# SCH_ESP-RotaryCell-Main-Carrier-Rev-A1_2.net
KiCad netlist of a schematic drawn in EasyEDA
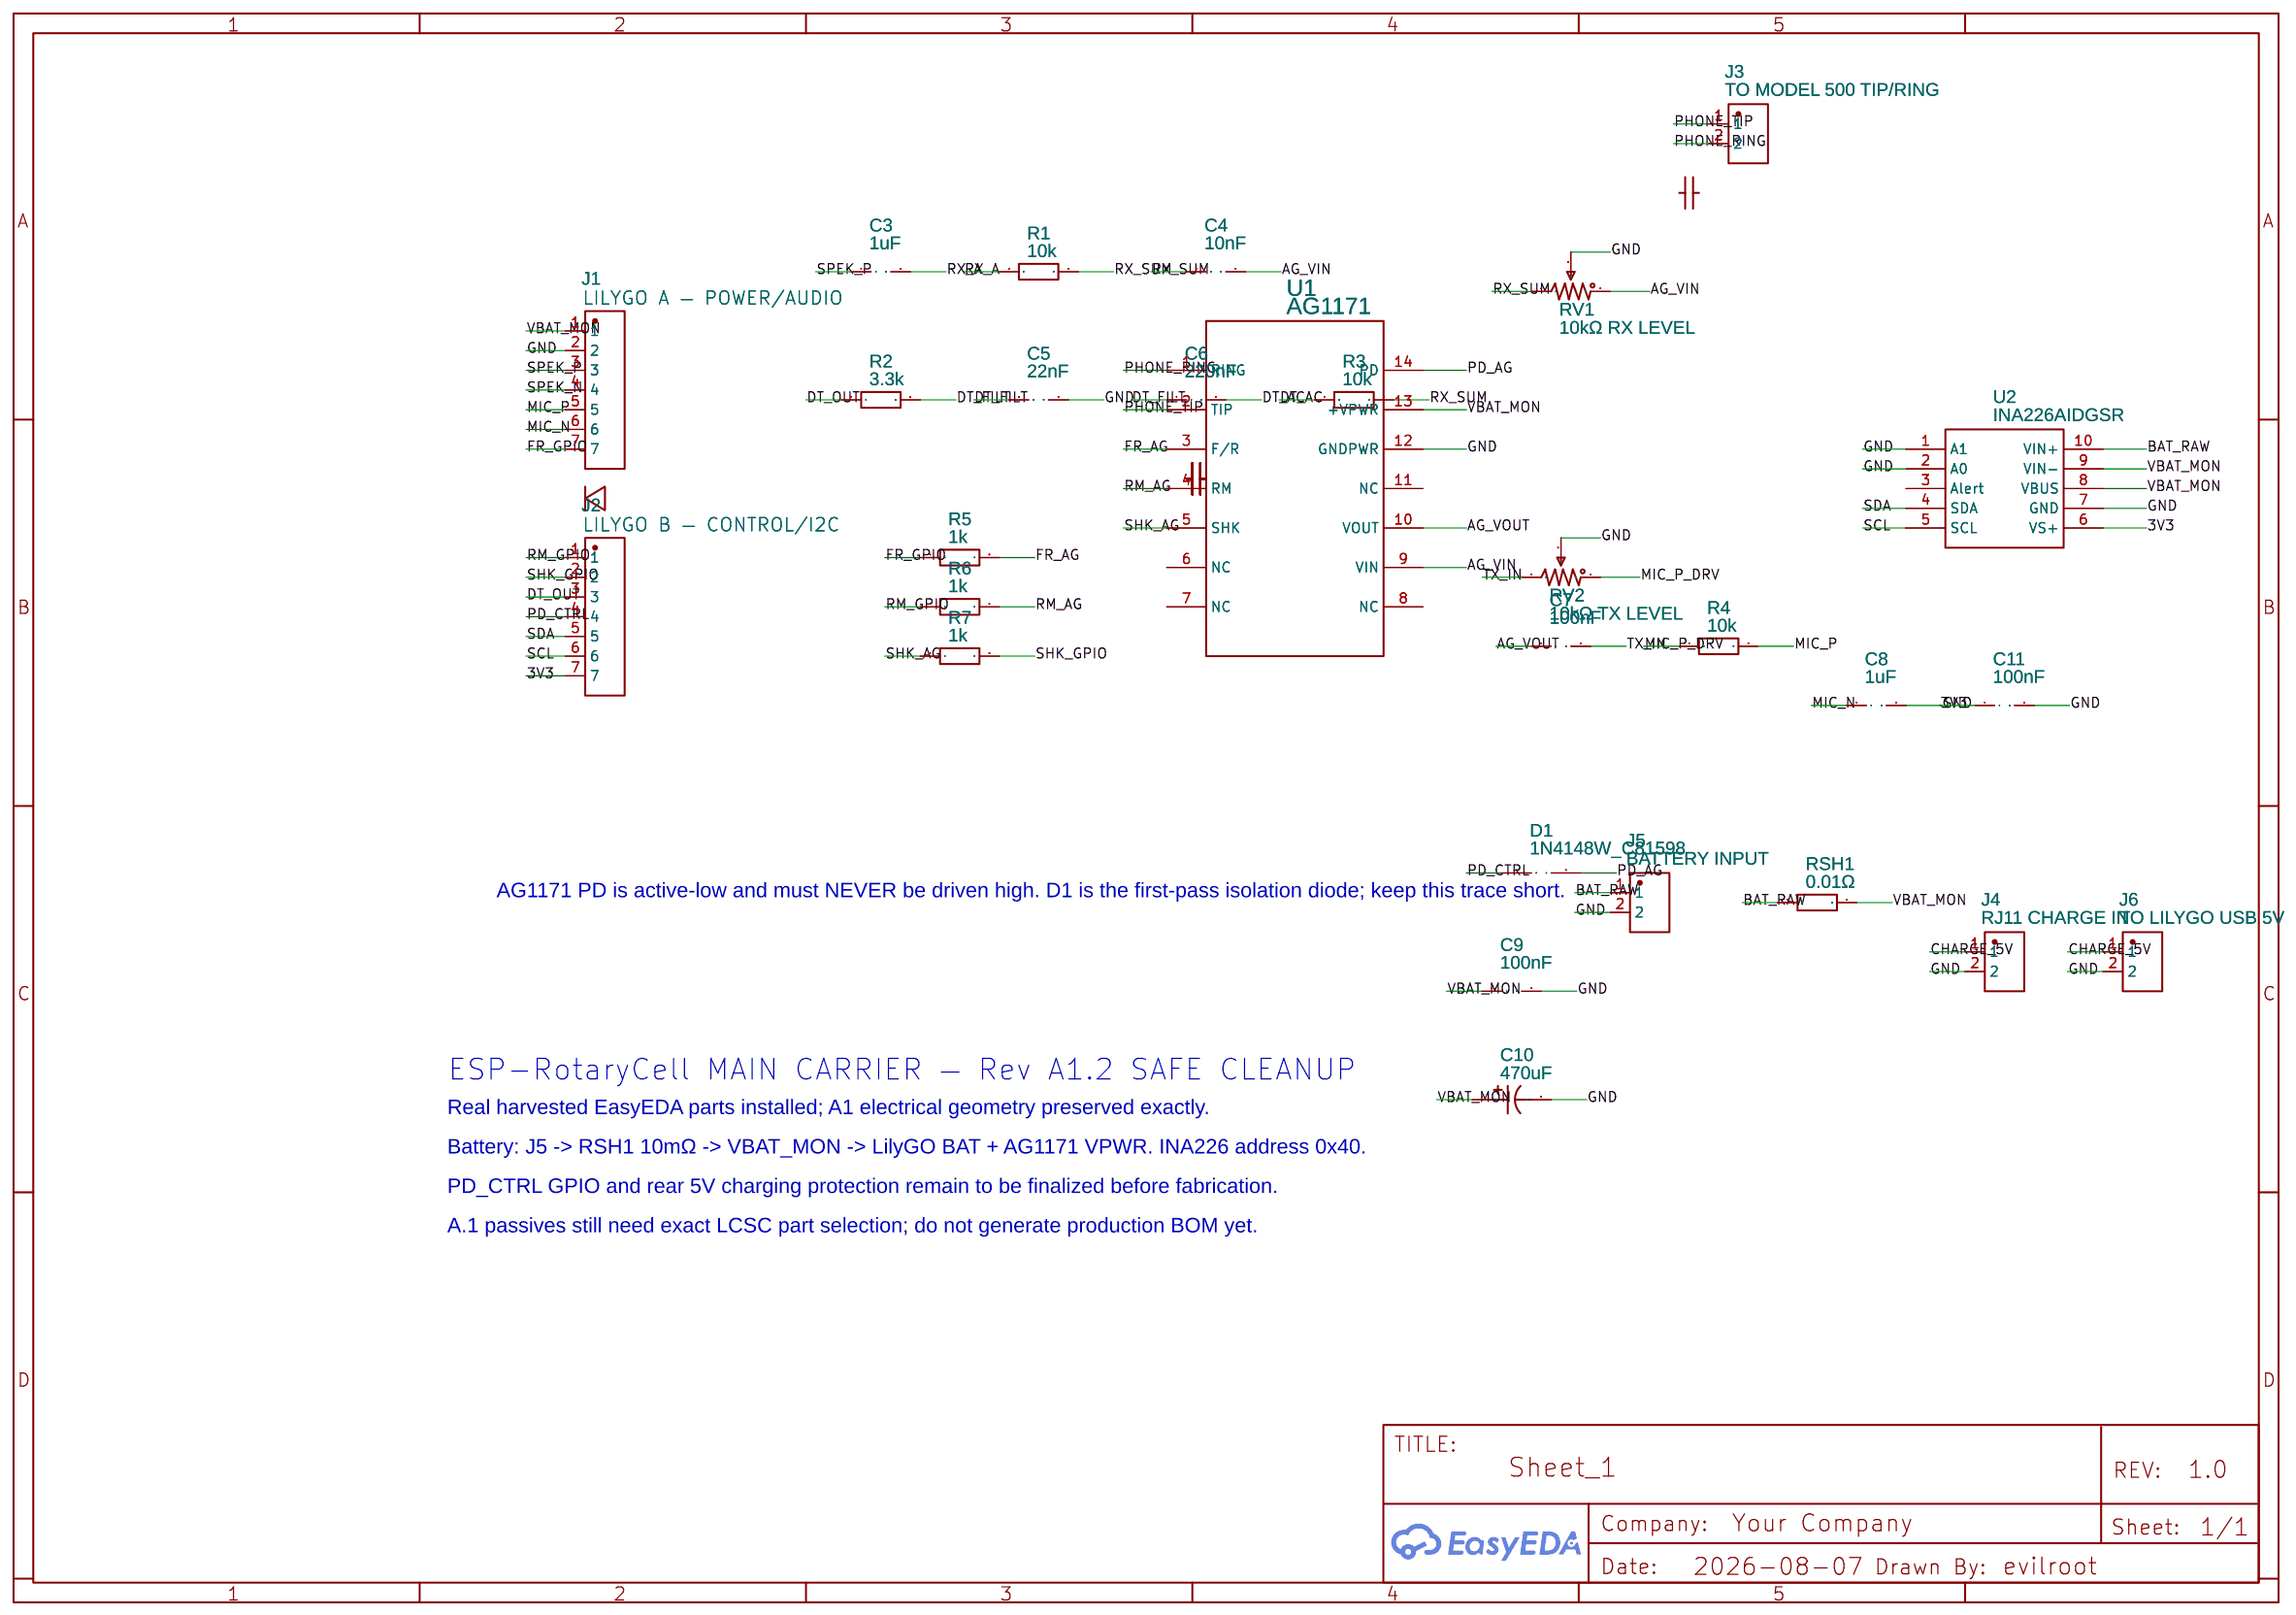
[diagram p0: schematic sheet]

(export (version "E")
  (design (tool "Eeschema 10.0.6"))
  (components
    (comp (ref "C3") (value "1uF") (libsource (lib "") (part "Unknown_440_-675")))
    (comp (ref "C4") (value "10nF") (libsource (lib "") (part "Unknown_610_-675")))
    (comp (ref "C5") (value "22nF") (libsource (lib "") (part "Unknown_520_-610")))
    (comp (ref "C6") (value "220nF") (libsource (lib "") (part "Unknown_600_-610")))
    (comp (ref "C7") (value "100nF") (libsource (lib "") (part "Unknown_785_-485")))
    (comp (ref "C8") (value "1uF") (libsource (lib "") (part "Unknown_945_-455")))
    (comp (ref "C9") (value "100nF") (libsource (lib "") (part "Unknown_760_-310")))
    (comp (ref "C10")
      (value "470uF")
      (fields
        (field (name "Manufacturer Part") "RYHT16V470UF5.5*11")
        (field (name "Manufacturer") "HONOR(荣誉)")
      )
      (libsource (lib "") (part "RYHT16V470UF5.5*11"))
    )
    (comp (ref "C11") (value "100nF") (libsource (lib "") (part "Unknown_1010_-455")))
    (comp (ref "D1")
      (value "1N4148W_C81598")
      (fields (field (name "Manufacturer Part") "1N4148W") (field (name "Manufacturer") "ST(先科)"))
      (libsource (lib "") (part "1N4148W_C81598"))
    )
    (comp (ref "J1")
      (value "LILYGO A — POWER/AUDIO")
      (fields
        (field (name "Manufacturer Part") "PM2.54-1x7PZZ-H8.5")
        (field (name "Manufacturer") "SHOU HAN(首韩)")
      )
      (libsource (lib "") (part "PM2.54-1X7PZZ-H8.5"))
    )
    (comp (ref "J2")
      (value "LILYGO B — CONTROL/I2C")
      (fields
        (field (name "Manufacturer Part") "PM2.54-1x7PZZ-H8.5")
        (field (name "Manufacturer") "SHOU HAN(首韩)")
      )
      (libsource (lib "") (part "PM2.54-1X7PZZ-H8.5"))
    )
    (comp (ref "J3")
      (value "TO MODEL 500 TIP/RING")
      (fields
        (field (name "Manufacturer Part") "HMT-2.54-1*2PM")
        (field (name "Manufacturer") "HMTCONN(华明通)")
      )
      (libsource (lib "") (part "HMT-2.54-1*2PM"))
    )
    (comp (ref "J4")
      (value "RJ11 CHARGE IN")
      (fields
        (field (name "Manufacturer Part") "HMT-2.54-1*2PM")
        (field (name "Manufacturer") "HMTCONN(华明通)")
      )
      (libsource (lib "") (part "HMT-2.54-1*2PM"))
    )
    (comp (ref "J5")
      (value "BATTERY INPUT")
      (fields
        (field (name "Manufacturer Part") "HMT-2.54-1*2PM")
        (field (name "Manufacturer") "HMTCONN(华明通)")
      )
      (libsource (lib "") (part "HMT-2.54-1*2PM"))
    )
    (comp (ref "J6")
      (value "TO LILYGO USB 5V")
      (fields
        (field (name "Manufacturer Part") "HMT-2.54-1*2PM")
        (field (name "Manufacturer") "HMTCONN(华明通)")
      )
      (libsource (lib "") (part "HMT-2.54-1*2PM"))
    )
    (comp (ref "R1") (value "10k") (libsource (lib "") (part "Unknown_520_-675")))
    (comp (ref "R2") (value "3.3k") (libsource (lib "") (part "Unknown_440_-610")))
    (comp (ref "R3") (value "10k") (libsource (lib "") (part "Unknown_680_-610")))
    (comp (ref "R4") (value "10k") (libsource (lib "") (part "Unknown_865_-485")))
    (comp (ref "R5") (value "1k") (libsource (lib "") (part "Unknown_480_-530")))
    (comp (ref "R6") (value "1k") (libsource (lib "") (part "Unknown_480_-505")))
    (comp (ref "R7") (value "1k") (libsource (lib "") (part "Unknown_480_-480")))
    (comp (ref "RSH1")
      (value "0.01Ω")
      (fields (field (name "Manufacturer Part") "MRF6432(2512)LR010JTS") (field (name "Manufacturer") "SUP"))
      (libsource (lib "") (part "MRF6432(2512)LR010JTS"))
    )
    (comp (ref "RV1")
      (value "10kΩ RX LEVEL")
      (fields (field (name "Manufacturer Part") "PS10KV50-103A3030") (field (name "Manufacturer") "Amphenol"))
      (libsource (lib "") (part "PS10KV50-103A3030"))
    )
    (comp (ref "RV2")
      (value "10kΩ TX LEVEL")
      (fields (field (name "Manufacturer Part") "PS10KV50-103A3030") (field (name "Manufacturer") "Amphenol"))
      (libsource (lib "") (part "PS10KV50-103A3030"))
    )
    (comp (ref "U1")
      (value "AG1171")
      (fields (field (name "Manufacturer Part") "Ag1171") (field (name "Manufacturer") "Silver Telecom"))
      (libsource (lib "") (part "AG1171"))
    )
    (comp (ref "U2")
      (value "INA226AIDGSR")
      (fields (field (name "Manufacturer") "TI(德州仪器)"))
      (libsource (lib "") (part "INA226AIDGSR"))
    )
  )
  (nets
    (net (code "1") (name "/3V3") (class "Default")
      (node (ref "C10") (pin "2") (pinfunction "2_2") (pintype "input"))
      (node (ref "C11") (pin "1") (pinfunction "1_1") (pintype "input"))
      (node (ref "C11") (pin "2") (pinfunction "2_2") (pintype "input"))
      (node (ref "C5") (pin "2") (pinfunction "2_2") (pintype "input"))
      (node (ref "C8") (pin "2") (pinfunction "2_2") (pintype "input"))
      (node (ref "C9") (pin "2") (pinfunction "2_2") (pintype "input"))
      (node (ref "J1") (pin "2") (pinfunction "2_2") (pintype "unspecified"))
      (node (ref "J2") (pin "7") (pinfunction "7_7") (pintype "unspecified"))
      (node (ref "J4") (pin "2") (pinfunction "2_2") (pintype "unspecified"))
      (node (ref "J5") (pin "2") (pinfunction "2_2") (pintype "unspecified"))
      (node (ref "J6") (pin "2") (pinfunction "2_2") (pintype "unspecified"))
      (node (ref "RV1") (pin "3") (pinfunction "3_3") (pintype "unspecified"))
      (node (ref "RV2") (pin "3") (pinfunction "3_3") (pintype "unspecified"))
      (node (ref "U1") (pin "12") (pinfunction "GNDPWR_12") (pintype "unspecified"))
      (node (ref "U2") (pin "1") (pinfunction "A1_1") (pintype "unspecified"))
      (node (ref "U2") (pin "2") (pinfunction "A0_2") (pintype "unspecified"))
      (node (ref "U2") (pin "6") (pinfunction "VS+_6") (pintype "unspecified"))
      (node (ref "U2") (pin "7") (pinfunction "GND_7") (pintype "unspecified"))
    )
    (net (code "2") (name "/AG_VIN") (class "Default")
      (node (ref "C4") (pin "2") (pinfunction "2_2") (pintype "input"))
      (node (ref "RV1") (pin "2") (pinfunction "2_2") (pintype "unspecified"))
      (node (ref "U1") (pin "9") (pinfunction "VIN_9") (pintype "unspecified"))
    )
    (net (code "3") (name "/AG_VOUT") (class "Default")
      (node (ref "C7") (pin "1") (pinfunction "1_1") (pintype "input"))
      (node (ref "U1") (pin "10") (pinfunction "VOUT_10") (pintype "unspecified"))
    )
    (net (code "4") (name "/BAT_RAW") (class "Default")
      (node (ref "J5") (pin "1") (pinfunction "1_1") (pintype "unspecified"))
      (node (ref "RSH1") (pin "1") (pinfunction "1_1") (pintype "input"))
      (node (ref "U2") (pin "10") (pinfunction "VIN+_10") (pintype "unspecified"))
    )
    (net (code "5") (name "/CHARGE_5V") (class "Default")
      (node (ref "J4") (pin "1") (pinfunction "1_1") (pintype "unspecified"))
      (node (ref "J6") (pin "1") (pinfunction "1_1") (pintype "unspecified"))
    )
    (net (code "6") (name "/DT_AC") (class "Default")
      (node (ref "C6") (pin "2") (pinfunction "2_2") (pintype "input"))
      (node (ref "R3") (pin "1") (pinfunction "1_1") (pintype "input"))
    )
    (net (code "7") (name "/DT_FILT") (class "Default")
      (node (ref "C5") (pin "1") (pinfunction "1_1") (pintype "input"))
      (node (ref "C6") (pin "1") (pinfunction "1_1") (pintype "input"))
      (node (ref "R2") (pin "2") (pinfunction "2_2") (pintype "input"))
    )
    (net (code "8") (name "/DT_OUT") (class "Default")
      (node (ref "J2") (pin "3") (pinfunction "3_3") (pintype "unspecified"))
      (node (ref "R2") (pin "1") (pinfunction "1_1") (pintype "input"))
    )
    (net (code "9") (name "/FR_AG") (class "Default")
      (node (ref "R5") (pin "2") (pinfunction "2_2") (pintype "input"))
      (node (ref "U1") (pin "3") (pinfunction "F/R_3") (pintype "unspecified"))
    )
    (net (code "10") (name "/FR_GPIO") (class "Default")
      (node (ref "J1") (pin "7") (pinfunction "7_7") (pintype "unspecified"))
      (node (ref "R5") (pin "1") (pinfunction "1_1") (pintype "input"))
    )
    (net (code "11") (name "/MIC_N") (class "Default")
      (node (ref "C8") (pin "1") (pinfunction "1_1") (pintype "input"))
      (node (ref "J1") (pin "6") (pinfunction "6_6") (pintype "unspecified"))
    )
    (net (code "12") (name "/MIC_P") (class "Default")
      (node (ref "J1") (pin "5") (pinfunction "5_5") (pintype "unspecified"))
      (node (ref "R4") (pin "2") (pinfunction "2_2") (pintype "input"))
    )
    (net (code "13") (name "/MIC_P_DRV") (class "Default")
      (node (ref "R4") (pin "1") (pinfunction "1_1") (pintype "input"))
      (node (ref "RV2") (pin "2") (pinfunction "2_2") (pintype "unspecified"))
    )
    (net (code "14") (name "/PD_AG") (class "Default")
      (node (ref "D1") (pin "2") (pinfunction "A_2") (pintype "unspecified"))
      (node (ref "U1") (pin "14") (pinfunction "PD_14") (pintype "unspecified"))
    )
    (net (code "15") (name "/PD_CTRL") (class "Default")
      (node (ref "D1") (pin "1") (pinfunction "K_1") (pintype "unspecified"))
      (node (ref "J2") (pin "4") (pinfunction "4_4") (pintype "unspecified"))
    )
    (net (code "16") (name "/PHONE_RING") (class "Default")
      (node (ref "J3") (pin "2") (pinfunction "2_2") (pintype "unspecified"))
      (node (ref "U1") (pin "1") (pinfunction "RING_1") (pintype "unspecified"))
    )
    (net (code "17") (name "/PHONE_TIP") (class "Default")
      (node (ref "J3") (pin "1") (pinfunction "1_1") (pintype "unspecified"))
      (node (ref "U1") (pin "2") (pinfunction "TIP_2") (pintype "unspecified"))
    )
    (net (code "18") (name "/RM_AG") (class "Default")
      (node (ref "R6") (pin "2") (pinfunction "2_2") (pintype "input"))
      (node (ref "U1") (pin "4") (pinfunction "RM_4") (pintype "unspecified"))
    )
    (net (code "19") (name "/RM_GPIO") (class "Default")
      (node (ref "J2") (pin "1") (pinfunction "1_1") (pintype "unspecified"))
      (node (ref "R6") (pin "1") (pinfunction "1_1") (pintype "input"))
    )
    (net (code "20") (name "/RX_A") (class "Default")
      (node (ref "C3") (pin "2") (pinfunction "2_2") (pintype "input"))
      (node (ref "R1") (pin "1") (pinfunction "1_1") (pintype "input"))
    )
    (net (code "21") (name "/RX_SUM") (class "Default")
      (node (ref "C4") (pin "1") (pinfunction "1_1") (pintype "input"))
      (node (ref "R1") (pin "2") (pinfunction "2_2") (pintype "input"))
      (node (ref "R3") (pin "2") (pinfunction "2_2") (pintype "input"))
      (node (ref "RV1") (pin "1") (pinfunction "1_1") (pintype "unspecified"))
    )
    (net (code "22") (name "/SCL") (class "Default")
      (node (ref "J2") (pin "6") (pinfunction "6_6") (pintype "unspecified"))
      (node (ref "U2") (pin "5") (pinfunction "SCL_5") (pintype "unspecified"))
    )
    (net (code "23") (name "/SDA") (class "Default")
      (node (ref "J2") (pin "5") (pinfunction "5_5") (pintype "unspecified"))
      (node (ref "U2") (pin "4") (pinfunction "SDA_4") (pintype "unspecified"))
    )
    (net (code "24") (name "/SHK_AG") (class "Default")
      (node (ref "R7") (pin "1") (pinfunction "1_1") (pintype "input"))
      (node (ref "U1") (pin "5") (pinfunction "SHK_5") (pintype "unspecified"))
    )
    (net (code "25") (name "/SHK_GPIO") (class "Default")
      (node (ref "J2") (pin "2") (pinfunction "2_2") (pintype "unspecified"))
      (node (ref "R7") (pin "2") (pinfunction "2_2") (pintype "input"))
    )
    (net (code "26") (name "/SPEK_N") (class "Default")
      (node (ref "J1") (pin "4") (pinfunction "4_4") (pintype "unspecified"))
    )
    (net (code "27") (name "/SPEK_P") (class "Default")
      (node (ref "C3") (pin "1") (pinfunction "1_1") (pintype "input"))
      (node (ref "J1") (pin "3") (pinfunction "3_3") (pintype "unspecified"))
    )
    (net (code "28") (name "/TX_IN") (class "Default")
      (node (ref "C7") (pin "2") (pinfunction "2_2") (pintype "input"))
      (node (ref "RV2") (pin "1") (pinfunction "1_1") (pintype "unspecified"))
    )
    (net (code "29") (name "/VBAT_MON") (class "Default")
      (node (ref "C10") (pin "1") (pinfunction "1_1") (pintype "input"))
      (node (ref "C9") (pin "1") (pinfunction "1_1") (pintype "input"))
      (node (ref "J1") (pin "1") (pinfunction "1_1") (pintype "unspecified"))
      (node (ref "RSH1") (pin "2") (pinfunction "2_2") (pintype "input"))
      (node (ref "U1") (pin "13") (pinfunction "+VPWR_13") (pintype "unspecified"))
      (node (ref "U2") (pin "8") (pinfunction "VBUS_8") (pintype "unspecified"))
      (node (ref "U2") (pin "9") (pinfunction "VIN-_9") (pintype "unspecified"))
    )
    (net (code "30") (name "unconnected-(U1-NC-Pad6)") (class "Default")
      (node (ref "U1") (pin "6") (pinfunction "NC_6") (pintype "unspecified"))
    )
    (net (code "31") (name "unconnected-(U1-NC-Pad7)") (class "Default")
      (node (ref "U1") (pin "7") (pinfunction "NC_7") (pintype "unspecified"))
    )
    (net (code "32") (name "unconnected-(U1-NC-Pad8)") (class "Default")
      (node (ref "U1") (pin "8") (pinfunction "NC_8") (pintype "unspecified"))
    )
    (net (code "33") (name "unconnected-(U1-NC-Pad11)") (class "Default")
      (node (ref "U1") (pin "11") (pinfunction "NC_11") (pintype "unspecified"))
    )
    (net (code "34") (name "unconnected-(U2-Alert-Pad3)") (class "Default")
      (node (ref "U2") (pin "3") (pinfunction "Alert_3") (pintype "unspecified"))
    )
  )
)
